# CSC_Connections_Temp.net
KiCad netlist of a schematic drawn in Altium Designer
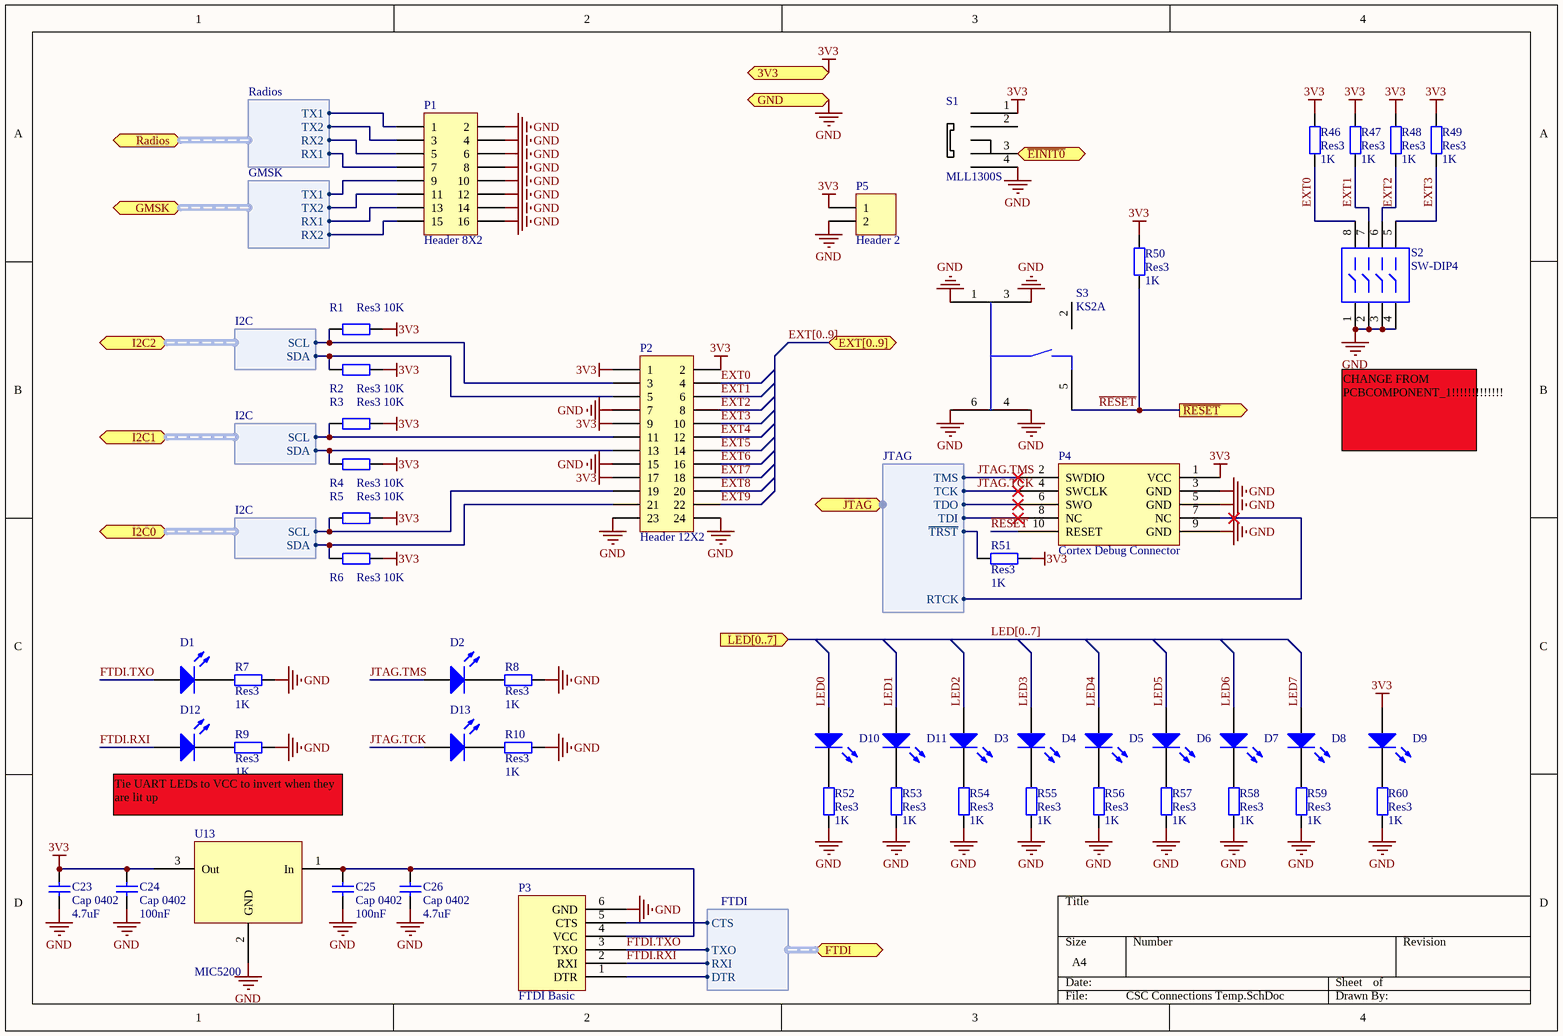
[diagram p0: CSC Connections Temp.SchDoc]

(export (version "E")
  (design (tool "Eeschema 10.0.6"))
  (components
    (comp (ref "C23")
      (value "Cap 0402")
      (footprint "CAPC1005X06L")
      (description "Capacitor")
      (fields (field (name "ALTIUM_VALUE") "4.7uF") (field (name "PUBLISHER") "Altium Limited"))
      (libsource (lib "CSC") (part "Cap 0402"))
    )
    (comp (ref "C24")
      (value "Cap 0402")
      (footprint "CAPC1005X06L")
      (description "Capacitor")
      (fields (field (name "ALTIUM_VALUE") "100nF") (field (name "PUBLISHER") "Altium Limited"))
      (libsource (lib "CSC") (part "Cap 0402"))
    )
    (comp (ref "C25")
      (value "Cap 0402")
      (footprint "CAPC1005X06L")
      (description "Capacitor")
      (fields (field (name "ALTIUM_VALUE") "100nF") (field (name "PUBLISHER") "Altium Limited"))
      (libsource (lib "CSC") (part "Cap 0402"))
    )
    (comp (ref "C26")
      (value "Cap 0402")
      (footprint "CAPC1005X06L")
      (description "Capacitor")
      (fields (field (name "ALTIUM_VALUE") "4.7uF") (field (name "PUBLISHER") "Altium Limited"))
      (libsource (lib "CSC") (part "Cap 0402"))
    )
    (comp (ref "D1")
      (value "LED - ASMT-Rx45")
      (footprint "ASMT-Rx45")
      (description "Typical INFRARED GaAs LED 0603")
      (fields (field (name "PUBLISHER") "Altium Limited"))
      (libsource (lib "CSC") (part "LED"))
    )
    (comp (ref "D2")
      (value "LED - ASMT-Rx45")
      (footprint "ASMT-Rx45")
      (description "Typical INFRARED GaAs LED 0603")
      (fields (field (name "PUBLISHER") "Altium Limited"))
      (libsource (lib "CSC") (part "LED"))
    )
    (comp (ref "D3")
      (value "LED - ASMT-Rx45")
      (footprint "ASMT-Rx45")
      (description "Typical INFRARED GaAs LED 0603")
      (fields (field (name "PUBLISHER") "Altium Limited"))
      (libsource (lib "CSC") (part "LED"))
    )
    (comp (ref "D4")
      (value "LED - ASMT-Rx45")
      (footprint "ASMT-Rx45")
      (description "Typical INFRARED GaAs LED 0603")
      (fields (field (name "PUBLISHER") "Altium Limited"))
      (libsource (lib "CSC") (part "LED"))
    )
    (comp (ref "D5")
      (value "LED - ASMT-Rx45")
      (footprint "ASMT-Rx45")
      (description "Typical INFRARED GaAs LED 0603")
      (fields (field (name "PUBLISHER") "Altium Limited"))
      (libsource (lib "CSC") (part "LED"))
    )
    (comp (ref "D6")
      (value "LED - ASMT-Rx45")
      (footprint "ASMT-Rx45")
      (description "Typical INFRARED GaAs LED 0603")
      (fields (field (name "PUBLISHER") "Altium Limited"))
      (libsource (lib "CSC") (part "LED"))
    )
    (comp (ref "D7")
      (value "LED - ASMT-Rx45")
      (footprint "ASMT-Rx45")
      (description "Typical INFRARED GaAs LED 0603")
      (fields (field (name "PUBLISHER") "Altium Limited"))
      (libsource (lib "CSC") (part "LED"))
    )
    (comp (ref "D8")
      (value "LED - ASMT-Rx45")
      (footprint "ASMT-Rx45")
      (description "Typical INFRARED GaAs LED 0603")
      (fields (field (name "PUBLISHER") "Altium Limited"))
      (libsource (lib "CSC") (part "LED"))
    )
    (comp (ref "D9")
      (value "LED - ASMT-Rx45")
      (footprint "ASMT-Rx45")
      (description "Typical INFRARED GaAs LED 0603")
      (fields (field (name "PUBLISHER") "Altium Limited"))
      (libsource (lib "CSC") (part "LED"))
    )
    (comp (ref "D10")
      (value "LED - ASMT-Rx45")
      (footprint "ASMT-Rx45")
      (description "Typical INFRARED GaAs LED 0603")
      (fields (field (name "PUBLISHER") "Altium Limited"))
      (libsource (lib "CSC") (part "LED"))
    )
    (comp (ref "D11")
      (value "LED - ASMT-Rx45")
      (footprint "ASMT-Rx45")
      (description "Typical INFRARED GaAs LED 0603")
      (fields (field (name "PUBLISHER") "Altium Limited"))
      (libsource (lib "CSC") (part "LED"))
    )
    (comp (ref "D12")
      (value "LED - ASMT-Rx45")
      (footprint "ASMT-Rx45")
      (description "Typical INFRARED GaAs LED 0603")
      (fields (field (name "PUBLISHER") "Altium Limited"))
      (libsource (lib "CSC") (part "LED"))
    )
    (comp (ref "D13")
      (value "LED - ASMT-Rx45")
      (footprint "ASMT-Rx45")
      (description "Typical INFRARED GaAs LED 0603")
      (fields (field (name "PUBLISHER") "Altium Limited"))
      (libsource (lib "CSC") (part "LED"))
    )
    (comp (ref "P1")
      (value "Header 8X2")
      (footprint "HDR2X8")
      (description "Header, 8-Pin, Dual row")
      (fields (field (name "PUBLISHER") "Altium Limited"))
      (libsource (lib "Miscellaneous Connectors") (part "Header 8X2"))
    )
    (comp (ref "P2")
      (value "Header 12X2")
      (footprint "HDR2X12")
      (description "Header, 12-Pin, Dual row")
      (fields (field (name "PUBLISHER") "Altium Limited"))
      (libsource (lib "Miscellaneous Connectors") (part "Header 12X2"))
    )
    (comp (ref "P3")
      (value "FTDI Basic")
      (footprint "FTDI BASIC")
      (libsource (lib "CSC") (part "FTDI Basic"))
    )
    (comp (ref "P4")
      (value "Cortex Debug Connector")
      (footprint "FTSH-105-01-L-DV-TR")
      (description "Mates with FFSD-05-D-12.00-01-N")
      (libsource (lib "CSC") (part "Cortex Debug Connector"))
    )
    (comp (ref "P5")
      (value "Header 2")
      (footprint "HDR1X2")
      (description "Header, 2-Pin")
      (fields (field (name "PUBLISHER") "Altium Limited"))
      (libsource (lib "Miscellaneous Connectors") (part "Header 2"))
    )
    (comp (ref "R1")
      (value "Res3")
      (footprint "RESC1005X06L")
      (description "Resistor")
      (fields (field (name "ALTIUM_VALUE") "10K") (field (name "PUBLISHER") "Altium Limited"))
      (libsource (lib "") (part "Res3_1"))
    )
    (comp (ref "R2")
      (value "Res3")
      (footprint "RESC1005X06L")
      (description "Resistor")
      (fields (field (name "ALTIUM_VALUE") "10K") (field (name "PUBLISHER") "Altium Limited"))
      (libsource (lib "") (part "Res3_1"))
    )
    (comp (ref "R3")
      (value "Res3")
      (footprint "RESC1005X06L")
      (description "Resistor")
      (fields (field (name "ALTIUM_VALUE") "10K") (field (name "PUBLISHER") "Altium Limited"))
      (libsource (lib "") (part "Res3_1"))
    )
    (comp (ref "R4")
      (value "Res3")
      (footprint "RESC1005X06L")
      (description "Resistor")
      (fields (field (name "ALTIUM_VALUE") "10K") (field (name "PUBLISHER") "Altium Limited"))
      (libsource (lib "") (part "Res3_1"))
    )
    (comp (ref "R5")
      (value "Res3")
      (footprint "RESC1005X06L")
      (description "Resistor")
      (fields (field (name "ALTIUM_VALUE") "10K") (field (name "PUBLISHER") "Altium Limited"))
      (libsource (lib "") (part "Res3_1"))
    )
    (comp (ref "R6")
      (value "Res3")
      (footprint "RESC1005X06L")
      (description "Resistor")
      (fields (field (name "ALTIUM_VALUE") "10K") (field (name "PUBLISHER") "Altium Limited"))
      (libsource (lib "") (part "Res3_1"))
    )
    (comp (ref "R7")
      (value "Res3")
      (footprint "RESC1005X06L")
      (description "Resistor")
      (fields (field (name "ALTIUM_VALUE") "1K") (field (name "PUBLISHER") "Altium Limited"))
      (libsource (lib "") (part "Res3_1"))
    )
    (comp (ref "R8")
      (value "Res3")
      (footprint "RESC1005X06L")
      (description "Resistor")
      (fields (field (name "ALTIUM_VALUE") "1K") (field (name "PUBLISHER") "Altium Limited"))
      (libsource (lib "") (part "Res3_1"))
    )
    (comp (ref "R9")
      (value "Res3")
      (footprint "RESC1005X06L")
      (description "Resistor")
      (fields (field (name "ALTIUM_VALUE") "1K") (field (name "PUBLISHER") "Altium Limited"))
      (libsource (lib "") (part "Res3_1"))
    )
    (comp (ref "R10")
      (value "Res3")
      (footprint "RESC1005X06L")
      (description "Resistor")
      (fields (field (name "ALTIUM_VALUE") "1K") (field (name "PUBLISHER") "Altium Limited"))
      (libsource (lib "") (part "Res3_1"))
    )
    (comp (ref "R46")
      (value "Res3")
      (footprint "RESC1005X06L")
      (description "Resistor")
      (fields (field (name "ALTIUM_VALUE") "1K") (field (name "PUBLISHER") "Altium Limited"))
      (libsource (lib "CSC") (part "Res3"))
    )
    (comp (ref "R47")
      (value "Res3")
      (footprint "RESC1005X06L")
      (description "Resistor")
      (fields (field (name "ALTIUM_VALUE") "1K") (field (name "PUBLISHER") "Altium Limited"))
      (libsource (lib "CSC") (part "Res3"))
    )
    (comp (ref "R48")
      (value "Res3")
      (footprint "RESC1005X06L")
      (description "Resistor")
      (fields (field (name "ALTIUM_VALUE") "1K") (field (name "PUBLISHER") "Altium Limited"))
      (libsource (lib "CSC") (part "Res3"))
    )
    (comp (ref "R49")
      (value "Res3")
      (footprint "RESC1005X06L")
      (description "Resistor")
      (fields (field (name "ALTIUM_VALUE") "1K") (field (name "PUBLISHER") "Altium Limited"))
      (libsource (lib "CSC") (part "Res3"))
    )
    (comp (ref "R50")
      (value "Res3")
      (footprint "RESC1005X06L")
      (description "Resistor")
      (fields (field (name "ALTIUM_VALUE") "1K") (field (name "PUBLISHER") "Altium Limited"))
      (libsource (lib "CSC") (part "Res3"))
    )
    (comp (ref "R51")
      (value "Res3")
      (footprint "RESC1005X06L")
      (description "Resistor")
      (fields (field (name "ALTIUM_VALUE") "1K") (field (name "PUBLISHER") "Altium Limited"))
      (libsource (lib "") (part "Res3_1"))
    )
    (comp (ref "R52")
      (value "Res3")
      (footprint "RESC1005X06L")
      (description "Resistor")
      (fields (field (name "ALTIUM_VALUE") "1K") (field (name "PUBLISHER") "Altium Limited"))
      (libsource (lib "CSC") (part "Res3"))
    )
    (comp (ref "R53")
      (value "Res3")
      (footprint "RESC1005X06L")
      (description "Resistor")
      (fields (field (name "ALTIUM_VALUE") "1K") (field (name "PUBLISHER") "Altium Limited"))
      (libsource (lib "CSC") (part "Res3"))
    )
    (comp (ref "R54")
      (value "Res3")
      (footprint "RESC1005X06L")
      (description "Resistor")
      (fields (field (name "ALTIUM_VALUE") "1K") (field (name "PUBLISHER") "Altium Limited"))
      (libsource (lib "CSC") (part "Res3"))
    )
    (comp (ref "R55")
      (value "Res3")
      (footprint "RESC1005X06L")
      (description "Resistor")
      (fields (field (name "ALTIUM_VALUE") "1K") (field (name "PUBLISHER") "Altium Limited"))
      (libsource (lib "CSC") (part "Res3"))
    )
    (comp (ref "R56")
      (value "Res3")
      (footprint "RESC1005X06L")
      (description "Resistor")
      (fields (field (name "ALTIUM_VALUE") "1K") (field (name "PUBLISHER") "Altium Limited"))
      (libsource (lib "CSC") (part "Res3"))
    )
    (comp (ref "R57")
      (value "Res3")
      (footprint "RESC1005X06L")
      (description "Resistor")
      (fields (field (name "ALTIUM_VALUE") "1K") (field (name "PUBLISHER") "Altium Limited"))
      (libsource (lib "CSC") (part "Res3"))
    )
    (comp (ref "R58")
      (value "Res3")
      (footprint "RESC1005X06L")
      (description "Resistor")
      (fields (field (name "ALTIUM_VALUE") "1K") (field (name "PUBLISHER") "Altium Limited"))
      (libsource (lib "CSC") (part "Res3"))
    )
    (comp (ref "R59")
      (value "Res3")
      (footprint "RESC1005X06L")
      (description "Resistor")
      (fields (field (name "ALTIUM_VALUE") "1K") (field (name "PUBLISHER") "Altium Limited"))
      (libsource (lib "CSC") (part "Res3"))
    )
    (comp (ref "R60")
      (value "Res3")
      (footprint "RESC1005X06L")
      (description "Resistor")
      (fields (field (name "ALTIUM_VALUE") "1K") (field (name "PUBLISHER") "Altium Limited"))
      (libsource (lib "CSC") (part "Res3"))
    )
    (comp (ref "S1")
      (value "MLL1300S")
      (footprint "MILL1300S")
      (description "Slide switch SP3T switch")
      (libsource (lib "CSC") (part "MLL1300S"))
    )
    (comp (ref "S2")
      (value "SW-DIP4")
      (footprint "PCBComponent_1")
      (description "DIP Switch - 1571983-5")
      (fields (field (name "PUBLISHER") "Altium Limited"))
      (libsource (lib "CSC") (part "SW-DIP4"))
    )
    (comp (ref "S3")
      (value "KS2A")
      (footprint "K5A2")
      (description "Tact Switch")
      (libsource (lib "CSC") (part "KS2A"))
    )
    (comp (ref "U13")
      (value "MIC5200")
      (footprint "SOT230P710X170-4L")
      (libsource (lib "CSC") (part "MIC5200"))
    )
  )
  (nets
    (net (code "6") (name "/CTS") (class "Default")
      (node (ref "P3") (pin "5") (pinfunction "CTS_5") (pintype "passive"))
    )
    (net (code "7") (name "/DTR") (class "Default")
      (node (ref "P3") (pin "1") (pinfunction "DTR_1") (pintype "passive"))
    )
    (net (code "8") (name "/EXT0") (class "Default")
      (node (ref "P2") (pin "4") (pinfunction "4_4") (pintype "passive"))
      (node (ref "R46") (pin "2") (pinfunction "2_2") (pintype "passive"))
      (node (ref "S2") (pin "8") (pinfunction "8_8") (pintype "passive"))
    )
    (net (code "9") (name "/EXT1") (class "Default")
      (node (ref "P2") (pin "6") (pinfunction "6_6") (pintype "passive"))
      (node (ref "R47") (pin "2") (pinfunction "2_2") (pintype "passive"))
      (node (ref "S2") (pin "7") (pinfunction "7_7") (pintype "passive"))
    )
    (net (code "10") (name "/EXT2") (class "Default")
      (node (ref "P2") (pin "8") (pinfunction "8_8") (pintype "passive"))
      (node (ref "R48") (pin "2") (pinfunction "2_2") (pintype "passive"))
      (node (ref "S2") (pin "6") (pinfunction "6_6") (pintype "passive"))
    )
    (net (code "11") (name "/EXT3") (class "Default")
      (node (ref "P2") (pin "10") (pinfunction "10_10") (pintype "passive"))
      (node (ref "R49") (pin "2") (pinfunction "2_2") (pintype "passive"))
      (node (ref "S2") (pin "5") (pinfunction "5_5") (pintype "passive"))
    )
    (net (code "12") (name "/EXT4") (class "Default")
      (node (ref "P2") (pin "12") (pinfunction "12_12") (pintype "passive"))
    )
    (net (code "13") (name "/EXT5") (class "Default")
      (node (ref "P2") (pin "14") (pinfunction "14_14") (pintype "passive"))
    )
    (net (code "14") (name "/EXT6") (class "Default")
      (node (ref "P2") (pin "16") (pinfunction "16_16") (pintype "passive"))
    )
    (net (code "15") (name "/EXT7") (class "Default")
      (node (ref "P2") (pin "18") (pinfunction "18_18") (pintype "passive"))
    )
    (net (code "16") (name "/EXT8") (class "Default")
      (node (ref "P2") (pin "20") (pinfunction "20_20") (pintype "passive"))
    )
    (net (code "17") (name "/EXT9") (class "Default")
      (node (ref "P2") (pin "22") (pinfunction "22_22") (pintype "passive"))
    )
    (net (code "19") (name "/FTDI.RXI") (class "Default")
      (node (ref "D12") (pin "1") (pinfunction "A_1") (pintype "passive"))
      (node (ref "P3") (pin "2") (pinfunction "RXI_2") (pintype "passive"))
    )
    (net (code "20") (name "/FTDI.TXO") (class "Default")
      (node (ref "D1") (pin "1") (pinfunction "A_1") (pintype "passive"))
      (node (ref "P3") (pin "3") (pinfunction "TXO_3") (pintype "passive"))
    )
    (net (code "21") (name "/JTAG.TCK") (class "Default")
      (node (ref "D13") (pin "1") (pinfunction "A_1") (pintype "passive"))
      (node (ref "P4") (pin "4") (pinfunction "SWCLK_4") (pintype "passive"))
    )
    (net (code "22") (name "/JTAG.TMS") (class "Default")
      (node (ref "D2") (pin "1") (pinfunction "A_1") (pintype "passive"))
      (node (ref "P4") (pin "2") (pinfunction "SWDIO_2") (pintype "passive"))
    )
    (net (code "23") (name "/LED0") (class "Default")
      (node (ref "D10") (pin "1") (pinfunction "A_1") (pintype "passive"))
    )
    (net (code "24") (name "/LED1") (class "Default")
      (node (ref "D11") (pin "1") (pinfunction "A_1") (pintype "passive"))
    )
    (net (code "25") (name "/LED2") (class "Default")
      (node (ref "D3") (pin "1") (pinfunction "A_1") (pintype "passive"))
    )
    (net (code "26") (name "/LED3") (class "Default")
      (node (ref "D4") (pin "1") (pinfunction "A_1") (pintype "passive"))
    )
    (net (code "27") (name "/LED4") (class "Default")
      (node (ref "D5") (pin "1") (pinfunction "A_1") (pintype "passive"))
    )
    (net (code "28") (name "/LED5") (class "Default")
      (node (ref "D6") (pin "1") (pinfunction "A_1") (pintype "passive"))
    )
    (net (code "29") (name "/LED6") (class "Default")
      (node (ref "D7") (pin "1") (pinfunction "A_1") (pintype "passive"))
    )
    (net (code "30") (name "/LED7") (class "Default")
      (node (ref "D8") (pin "1") (pinfunction "A_1") (pintype "passive"))
    )
    (net (code "32") (name "/RTCK") (class "Default")
      (node (ref "P4") (pin "7") (pinfunction "NC_7") (pintype "passive"))
    )
    (net (code "33") (name "/TDI") (class "Default")
      (node (ref "P4") (pin "8") (pinfunction "NC_8") (pintype "passive+no_connect"))
    )
    (net (code "34") (name "/TDO") (class "Default")
      (node (ref "P4") (pin "6") (pinfunction "SWO_6") (pintype "passive+no_connect"))
    )
    (net (code "40") (name "/~{EINIT0}") (class "Default")
      (node (ref "S1") (pin "3") (pinfunction "3_3") (pintype "passive"))
    )
    (net (code "41") (name "/~{RESET}") (class "Default")
      (node (ref "P4") (pin "10") (pinfunction "RESET_10") (pintype "passive"))
      (node (ref "R50") (pin "2") (pinfunction "2_2") (pintype "passive"))
      (node (ref "S3") (pin "5") (pinfunction "5_5") (pintype "passive"))
    )
    (net (code "42") (name "/~{TRST}") (class "Default")
      (node (ref "R51") (pin "1") (pinfunction "1_1") (pintype "passive"))
    )
    (net (code "43") (name "3V3") (class "Default")
      (node (ref "C23") (pin "2") (pinfunction "2_2") (pintype "passive"))
      (node (ref "C24") (pin "2") (pinfunction "2_2") (pintype "passive"))
      (node (ref "D9") (pin "1") (pinfunction "A_1") (pintype "passive"))
      (node (ref "P2") (pin "1") (pinfunction "1_1") (pintype "passive"))
      (node (ref "P2") (pin "17") (pinfunction "17_17") (pintype "passive"))
      (node (ref "P2") (pin "2") (pinfunction "2_2") (pintype "passive"))
      (node (ref "P2") (pin "9") (pinfunction "9_9") (pintype "passive"))
      (node (ref "P4") (pin "1") (pinfunction "VCC_1") (pintype "passive"))
      (node (ref "P5") (pin "1") (pinfunction "1_1") (pintype "passive"))
      (node (ref "R1") (pin "2") (pinfunction "2_2") (pintype "passive"))
      (node (ref "R2") (pin "2") (pinfunction "2_2") (pintype "passive"))
      (node (ref "R3") (pin "2") (pinfunction "2_2") (pintype "passive"))
      (node (ref "R4") (pin "2") (pinfunction "2_2") (pintype "passive"))
      (node (ref "R46") (pin "1") (pinfunction "1_1") (pintype "passive"))
      (node (ref "R47") (pin "1") (pinfunction "1_1") (pintype "passive"))
      (node (ref "R48") (pin "1") (pinfunction "1_1") (pintype "passive"))
      (node (ref "R49") (pin "1") (pinfunction "1_1") (pintype "passive"))
      (node (ref "R5") (pin "2") (pinfunction "2_2") (pintype "passive"))
      (node (ref "R50") (pin "1") (pinfunction "1_1") (pintype "passive"))
      (node (ref "R51") (pin "2") (pinfunction "2_2") (pintype "passive"))
      (node (ref "R6") (pin "2") (pinfunction "2_2") (pintype "passive"))
      (node (ref "S1") (pin "1") (pinfunction "1_1") (pintype "passive"))
      (node (ref "U13") (pin "3") (pinfunction "Out_3") (pintype "power_in"))
    )
    (net (code "44") (name "GND") (class "Default")
      (node (ref "C23") (pin "1") (pinfunction "1_1") (pintype "passive"))
      (node (ref "C24") (pin "1") (pinfunction "1_1") (pintype "passive"))
      (node (ref "C25") (pin "1") (pinfunction "1_1") (pintype "passive"))
      (node (ref "C26") (pin "1") (pinfunction "1_1") (pintype "passive"))
      (node (ref "P1") (pin "10") (pinfunction "10_10") (pintype "passive"))
      (node (ref "P1") (pin "12") (pinfunction "12_12") (pintype "passive"))
      (node (ref "P1") (pin "14") (pinfunction "14_14") (pintype "passive"))
      (node (ref "P1") (pin "16") (pinfunction "16_16") (pintype "passive"))
      (node (ref "P1") (pin "2") (pinfunction "2_2") (pintype "passive"))
      (node (ref "P1") (pin "4") (pinfunction "4_4") (pintype "passive"))
      (node (ref "P1") (pin "6") (pinfunction "6_6") (pintype "passive"))
      (node (ref "P1") (pin "8") (pinfunction "8_8") (pintype "passive"))
      (node (ref "P2") (pin "15") (pinfunction "15_15") (pintype "passive"))
      (node (ref "P2") (pin "23") (pinfunction "23_23") (pintype "passive"))
      (node (ref "P2") (pin "24") (pinfunction "24_24") (pintype "passive"))
      (node (ref "P2") (pin "7") (pinfunction "7_7") (pintype "passive"))
      (node (ref "P3") (pin "6") (pinfunction "GND_6") (pintype "passive"))
      (node (ref "P4") (pin "3") (pinfunction "GND_3") (pintype "passive"))
      (node (ref "P4") (pin "5") (pinfunction "GND_5") (pintype "passive"))
      (node (ref "P4") (pin "9") (pinfunction "GND_9") (pintype "passive"))
      (node (ref "P5") (pin "2") (pinfunction "2_2") (pintype "passive"))
      (node (ref "R10") (pin "2") (pinfunction "2_2") (pintype "passive"))
      (node (ref "R52") (pin "2") (pinfunction "2_2") (pintype "passive"))
      (node (ref "R53") (pin "2") (pinfunction "2_2") (pintype "passive"))
      (node (ref "R54") (pin "2") (pinfunction "2_2") (pintype "passive"))
      (node (ref "R55") (pin "2") (pinfunction "2_2") (pintype "passive"))
      (node (ref "R56") (pin "2") (pinfunction "2_2") (pintype "passive"))
      (node (ref "R57") (pin "2") (pinfunction "2_2") (pintype "passive"))
      (node (ref "R58") (pin "2") (pinfunction "2_2") (pintype "passive"))
      (node (ref "R59") (pin "2") (pinfunction "2_2") (pintype "passive"))
      (node (ref "R60") (pin "2") (pinfunction "2_2") (pintype "passive"))
      (node (ref "R7") (pin "2") (pinfunction "2_2") (pintype "passive"))
      (node (ref "R8") (pin "2") (pinfunction "2_2") (pintype "passive"))
      (node (ref "R9") (pin "2") (pinfunction "2_2") (pintype "passive"))
      (node (ref "S1") (pin "4") (pinfunction "4_4") (pintype "passive"))
      (node (ref "S2") (pin "1") (pinfunction "1_1") (pintype "passive"))
      (node (ref "S2") (pin "2") (pinfunction "2_2") (pintype "passive"))
      (node (ref "S2") (pin "3") (pinfunction "3_3") (pintype "passive"))
      (node (ref "S2") (pin "4") (pinfunction "4_4") (pintype "passive"))
      (node (ref "S3") (pin "1") (pinfunction "1_1") (pintype "power_in"))
      (node (ref "S3") (pin "3") (pinfunction "3_3") (pintype "power_in"))
      (node (ref "S3") (pin "4") (pinfunction "4_4") (pintype "power_in"))
      (node (ref "S3") (pin "6") (pinfunction "6_6") (pintype "power_in"))
      (node (ref "U13") (pin "2") (pinfunction "GND_2") (pintype "power_in"))
    )
    (net (code "45") (name "Net-(D1-K)") (class "Default")
      (node (ref "D1") (pin "2") (pinfunction "K_2") (pintype "passive"))
      (node (ref "R7") (pin "1") (pinfunction "1_1") (pintype "passive"))
    )
    (net (code "46") (name "Net-(D2-K)") (class "Default")
      (node (ref "D2") (pin "2") (pinfunction "K_2") (pintype "passive"))
      (node (ref "R8") (pin "1") (pinfunction "1_1") (pintype "passive"))
    )
    (net (code "47") (name "Net-(D3-K)") (class "Default")
      (node (ref "D3") (pin "2") (pinfunction "K_2") (pintype "passive"))
      (node (ref "R54") (pin "1") (pinfunction "1_1") (pintype "passive"))
    )
    (net (code "48") (name "Net-(D4-K)") (class "Default")
      (node (ref "D4") (pin "2") (pinfunction "K_2") (pintype "passive"))
      (node (ref "R55") (pin "1") (pinfunction "1_1") (pintype "passive"))
    )
    (net (code "49") (name "Net-(D5-K)") (class "Default")
      (node (ref "D5") (pin "2") (pinfunction "K_2") (pintype "passive"))
      (node (ref "R56") (pin "1") (pinfunction "1_1") (pintype "passive"))
    )
    (net (code "50") (name "Net-(D6-K)") (class "Default")
      (node (ref "D6") (pin "2") (pinfunction "K_2") (pintype "passive"))
      (node (ref "R57") (pin "1") (pinfunction "1_1") (pintype "passive"))
    )
    (net (code "51") (name "Net-(D7-K)") (class "Default")
      (node (ref "D7") (pin "2") (pinfunction "K_2") (pintype "passive"))
      (node (ref "R58") (pin "1") (pinfunction "1_1") (pintype "passive"))
    )
    (net (code "52") (name "Net-(D8-K)") (class "Default")
      (node (ref "D8") (pin "2") (pinfunction "K_2") (pintype "passive"))
      (node (ref "R59") (pin "1") (pinfunction "1_1") (pintype "passive"))
    )
    (net (code "53") (name "Net-(D9-K)") (class "Default")
      (node (ref "D9") (pin "2") (pinfunction "K_2") (pintype "passive"))
      (node (ref "R60") (pin "1") (pinfunction "1_1") (pintype "passive"))
    )
    (net (code "54") (name "Net-(D10-K)") (class "Default")
      (node (ref "D10") (pin "2") (pinfunction "K_2") (pintype "passive"))
      (node (ref "R52") (pin "1") (pinfunction "1_1") (pintype "passive"))
    )
    (net (code "55") (name "Net-(D11-K)") (class "Default")
      (node (ref "D11") (pin "2") (pinfunction "K_2") (pintype "passive"))
      (node (ref "R53") (pin "1") (pinfunction "1_1") (pintype "passive"))
    )
    (net (code "56") (name "Net-(D12-K)") (class "Default")
      (node (ref "D12") (pin "2") (pinfunction "K_2") (pintype "passive"))
      (node (ref "R9") (pin "1") (pinfunction "1_1") (pintype "passive"))
    )
    (net (code "57") (name "Net-(D13-K)") (class "Default")
      (node (ref "D13") (pin "2") (pinfunction "K_2") (pintype "passive"))
      (node (ref "R10") (pin "1") (pinfunction "1_1") (pintype "passive"))
    )
    (net (code "58") (name "Net-(P2-Pad3)") (class "Default")
      (node (ref "P2") (pin "3") (pinfunction "3_3") (pintype "passive"))
      (node (ref "R1") (pin "1") (pinfunction "1_1") (pintype "passive"))
    )
    (net (code "59") (name "Net-(P2-Pad5)") (class "Default")
      (node (ref "P2") (pin "5") (pinfunction "5_5") (pintype "passive"))
      (node (ref "R2") (pin "1") (pinfunction "1_1") (pintype "passive"))
    )
    (net (code "60") (name "Net-(P2-Pad11)") (class "Default")
      (node (ref "P2") (pin "11") (pinfunction "11_11") (pintype "passive"))
      (node (ref "R3") (pin "1") (pinfunction "1_1") (pintype "passive"))
    )
    (net (code "61") (name "Net-(P2-Pad13)") (class "Default")
      (node (ref "P2") (pin "13") (pinfunction "13_13") (pintype "passive"))
      (node (ref "R4") (pin "1") (pinfunction "1_1") (pintype "passive"))
    )
    (net (code "62") (name "Net-(P2-Pad19)") (class "Default")
      (node (ref "P2") (pin "19") (pinfunction "19_19") (pintype "passive"))
      (node (ref "R5") (pin "1") (pinfunction "1_1") (pintype "passive"))
    )
    (net (code "63") (name "Net-(P2-Pad21)") (class "Default")
      (node (ref "P2") (pin "21") (pinfunction "21_21") (pintype "passive"))
      (node (ref "R6") (pin "1") (pinfunction "1_1") (pintype "passive"))
    )
    (net (code "64") (name "Net-(P3-VCC)") (class "Default")
      (node (ref "C25") (pin "2") (pinfunction "2_2") (pintype "passive"))
      (node (ref "C26") (pin "2") (pinfunction "2_2") (pintype "passive"))
      (node (ref "P3") (pin "4") (pinfunction "VCC_4") (pintype "passive"))
      (node (ref "U13") (pin "1") (pinfunction "In_1") (pintype "power_in"))
    )
    (net (code "65") (name "unconnected-(P1-Pad1)") (class "Default")
      (node (ref "P1") (pin "1") (pinfunction "1_1") (pintype "passive"))
    )
    (net (code "66") (name "unconnected-(P1-Pad3)") (class "Default")
      (node (ref "P1") (pin "3") (pinfunction "3_3") (pintype "passive"))
    )
    (net (code "67") (name "unconnected-(P1-Pad5)") (class "Default")
      (node (ref "P1") (pin "5") (pinfunction "5_5") (pintype "passive"))
    )
    (net (code "68") (name "unconnected-(P1-Pad7)") (class "Default")
      (node (ref "P1") (pin "7") (pinfunction "7_7") (pintype "passive"))
    )
    (net (code "69") (name "unconnected-(P1-Pad9)") (class "Default")
      (node (ref "P1") (pin "9") (pinfunction "9_9") (pintype "passive"))
    )
    (net (code "70") (name "unconnected-(P1-Pad11)") (class "Default")
      (node (ref "P1") (pin "11") (pinfunction "11_11") (pintype "passive"))
    )
    (net (code "71") (name "unconnected-(P1-Pad13)") (class "Default")
      (node (ref "P1") (pin "13") (pinfunction "13_13") (pintype "passive"))
    )
    (net (code "72") (name "unconnected-(P1-Pad15)") (class "Default")
      (node (ref "P1") (pin "15") (pinfunction "15_15") (pintype "passive"))
    )
    (net (code "73") (name "unconnected-(S1-Pad2)") (class "Default")
      (node (ref "S1") (pin "2") (pinfunction "2_2") (pintype "passive"))
    )
    (net (code "74") (name "unconnected-(S3-Pad2)") (class "Default")
      (node (ref "S3") (pin "2") (pinfunction "2_2") (pintype "power_in"))
    )
  )
)
